# Mezzanine_Dual_H-Bridge.net
KiCad netlist of a schematic drawn in EAGLE
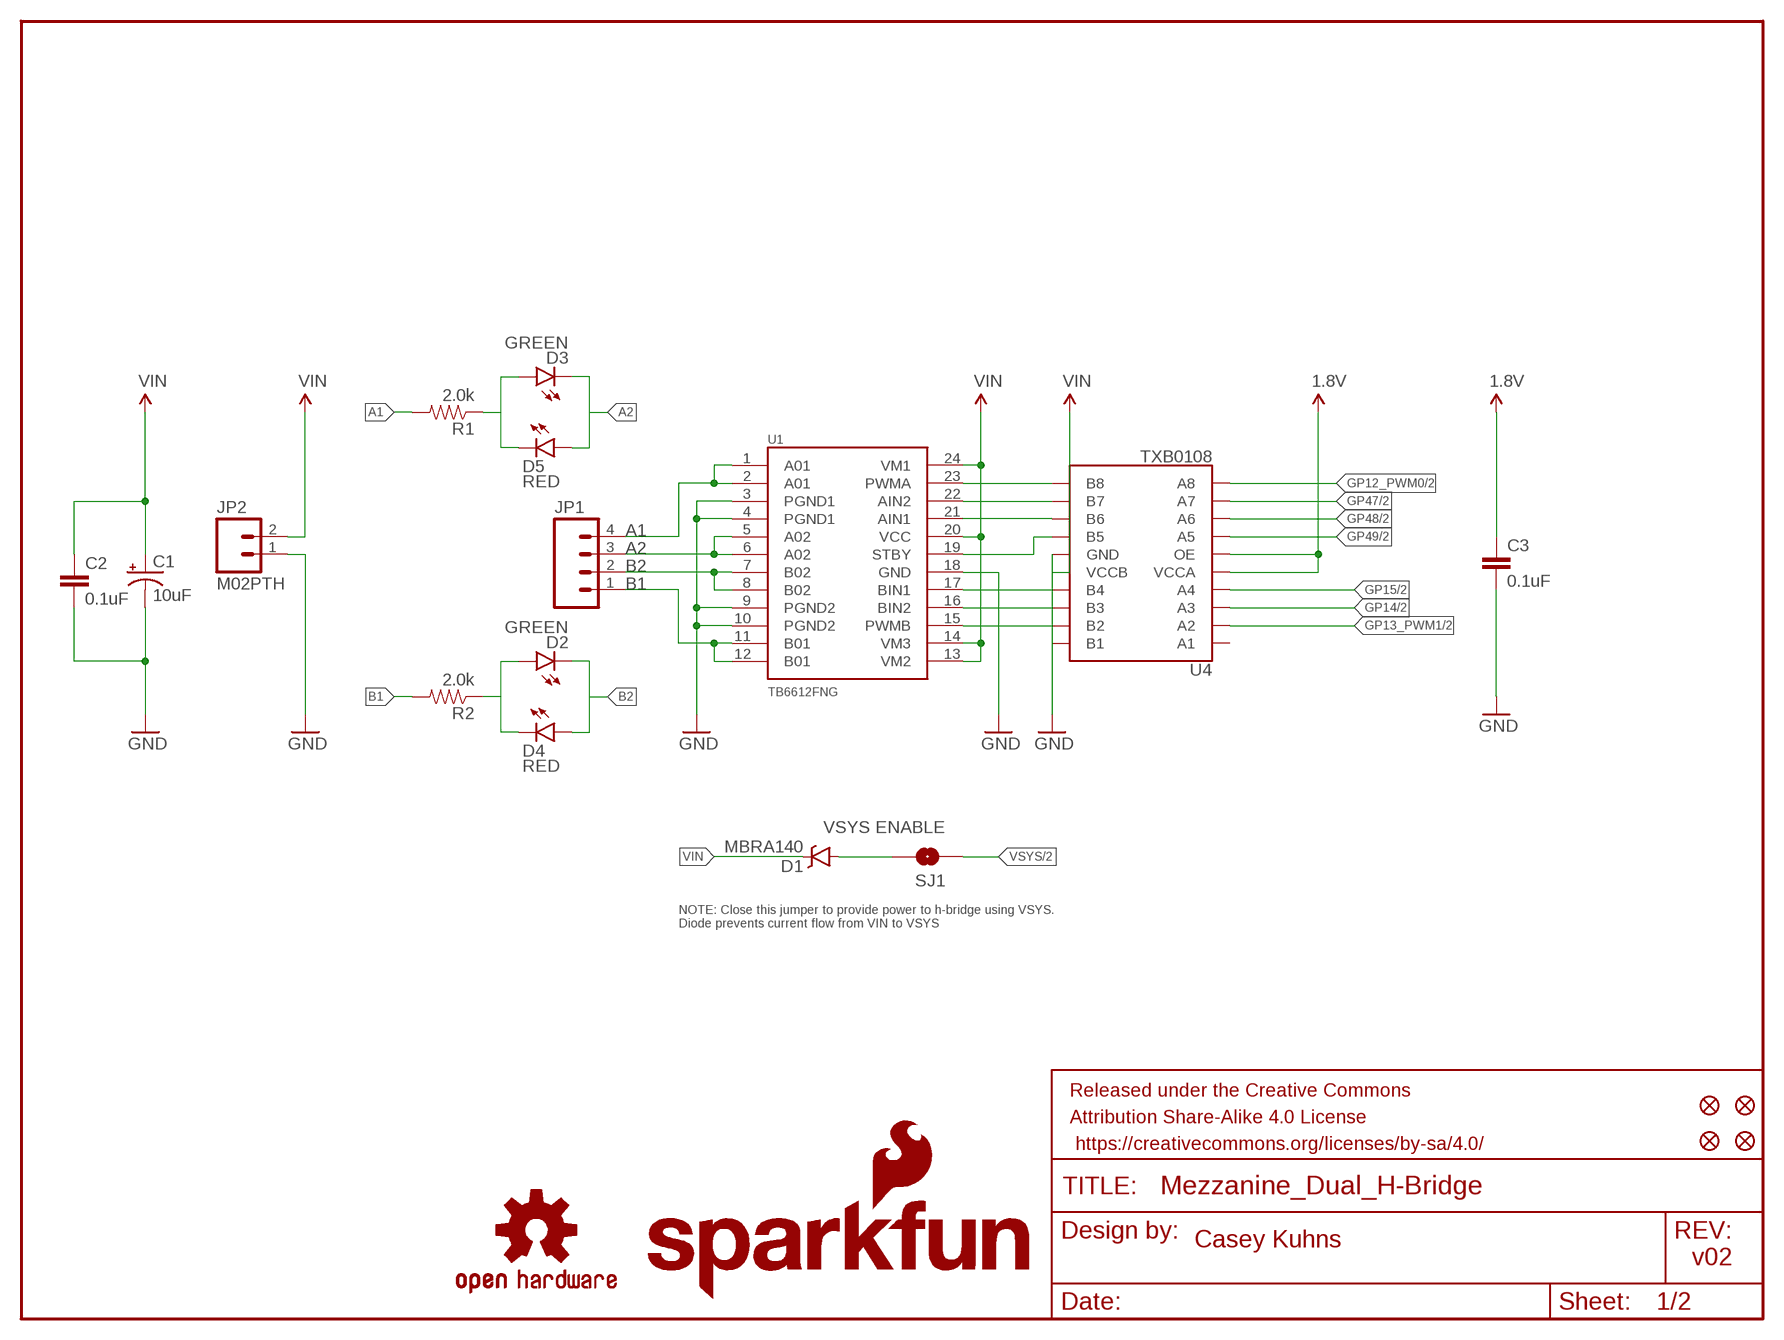
[diagram p0: schematic, sheet 1]
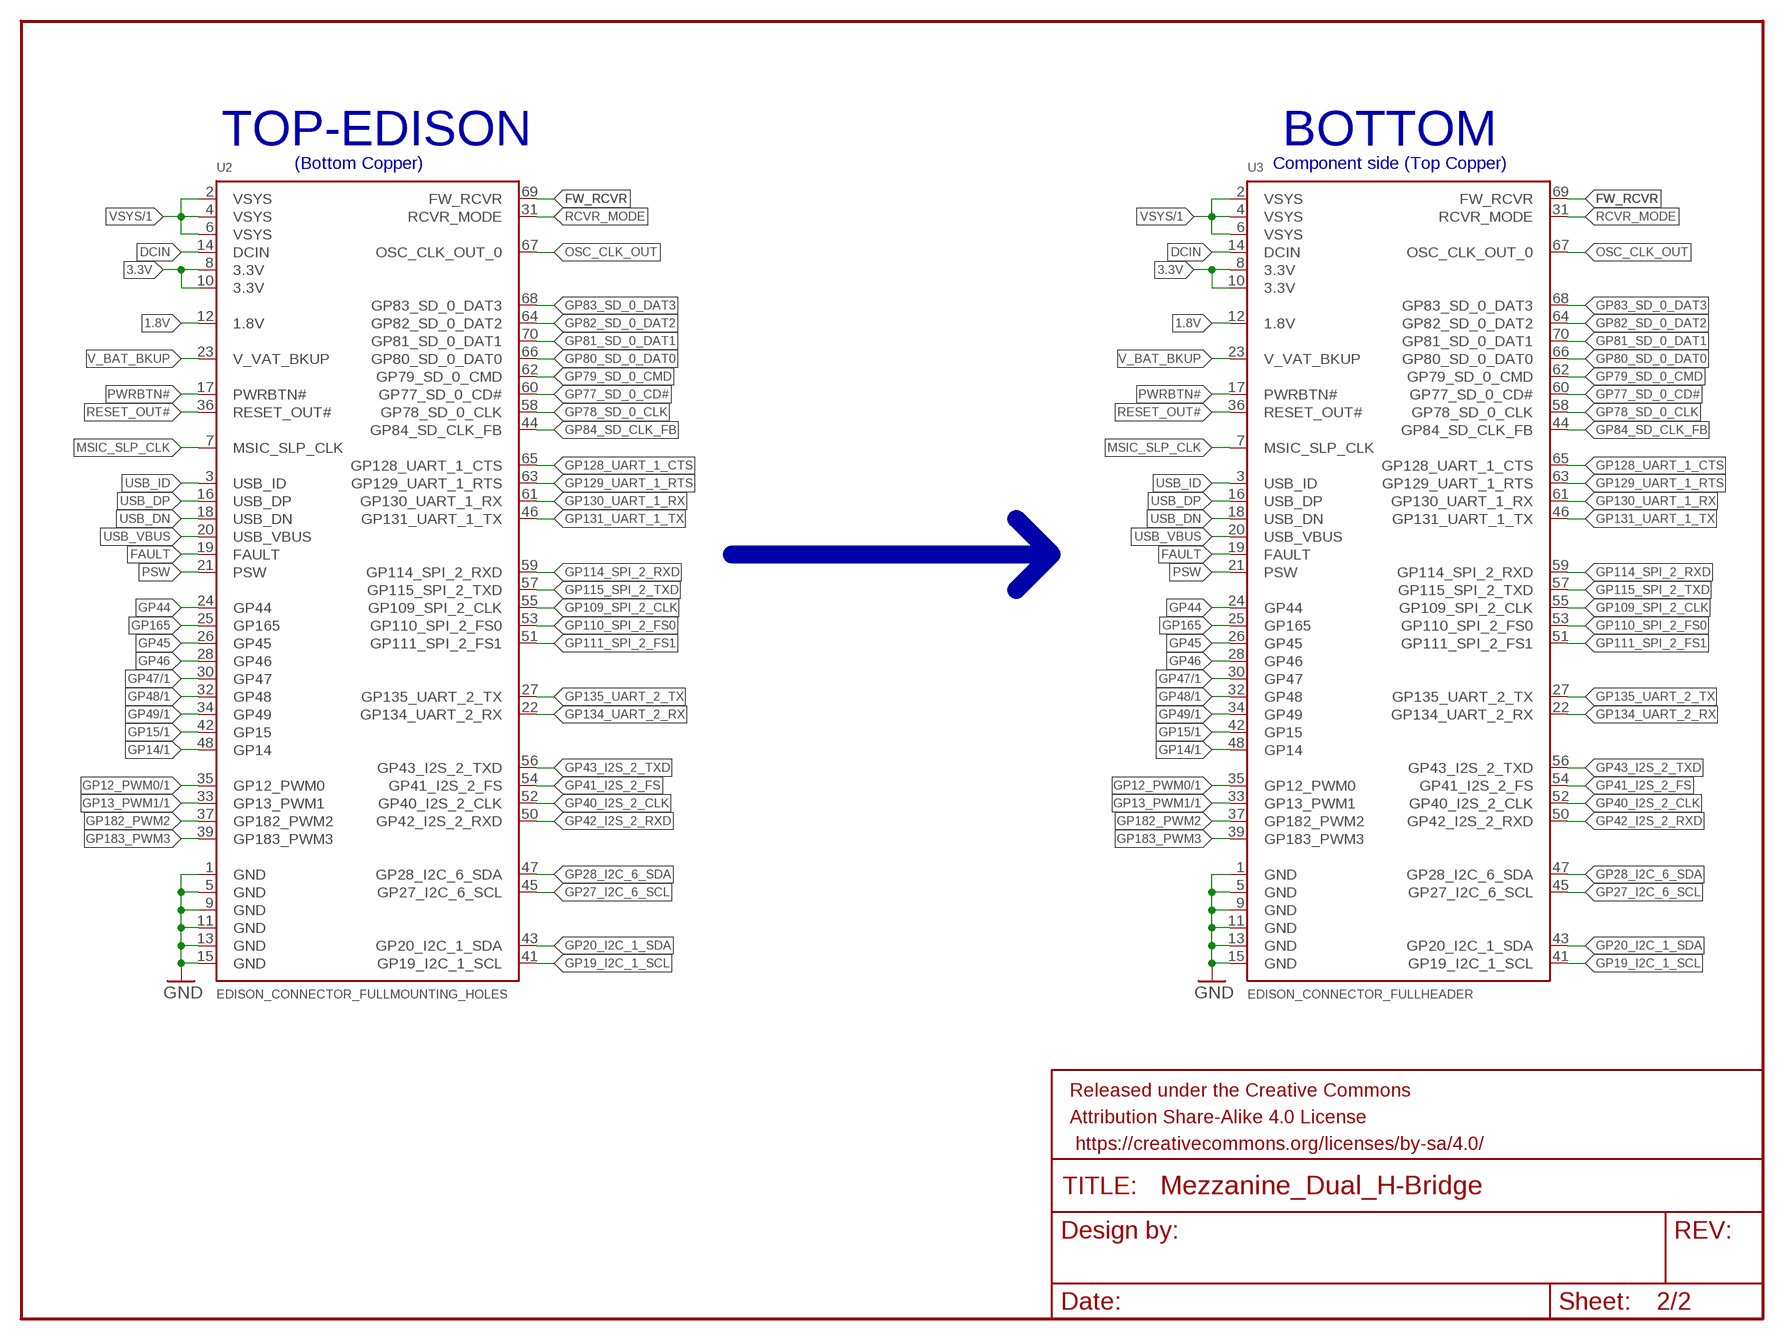
[diagram p1: schematic, sheet 2]

(export (version "E")
  (design (tool "Eeschema 10.0.6"))
  (components
    (comp (ref "FRAME2")
      (value "FRAME-LETTER")
      (footprint "eagle-import:CREATIVE_COMMONS")
      (libsource (lib "eagle-import") (part "FRAME-LETTER"))
    )
    (comp (ref "U2")
      (value "EDISON_CONNECTOR_FULLMOUNTING_HOLES")
      (footprint "eagle-import:EDISON_DAUGHTER")
      (libsource (lib "eagle-import") (part "EDISON_CONNECTOR_FULLMOUNTING_HOLES"))
    )
    (comp (ref "U3")
      (value "EDISON_CONNECTOR_FULLHEADER")
      (footprint "eagle-import:DF40C-70DP-0.4(51)")
      (libsource (lib "eagle-import") (part "EDISON_CONNECTOR_FULLHEADER"))
    )
    (comp (ref "C1")
      (value "10uF")
      (footprint "eagle-import:EIA3216")
      (libsource (lib "eagle-import") (part "10UF-16V-10%(TANT)"))
    )
    (comp (ref "C2")
      (value "0.1uF")
      (footprint "eagle-import:0603-CAP")
      (libsource (lib "eagle-import") (part "0.1UF-25V(+80/-20%)(0603)"))
    )
    (comp (ref "C3")
      (value "0.1uF")
      (footprint "eagle-import:0603-CAP")
      (libsource (lib "eagle-import") (part "0.1UF-25V(+80/-20%)(0603)"))
    )
    (comp (ref "D1")
      (value "MBRA140")
      (footprint "eagle-import:SMA-DIODE")
      (libsource (lib "eagle-import") (part "DIODE-SCHOTTKY-MBRA140"))
    )
    (comp (ref "D2")
      (value "GREEN")
      (footprint "eagle-import:LED-0603")
      (libsource (lib "eagle-import") (part "LED-GREEN0603"))
    )
    (comp (ref "D3")
      (value "GREEN")
      (footprint "eagle-import:LED-0603")
      (libsource (lib "eagle-import") (part "LED-GREEN0603"))
    )
    (comp (ref "D4")
      (value "RED")
      (footprint "eagle-import:LED-0603")
      (libsource (lib "eagle-import") (part "LED-RED0603"))
    )
    (comp (ref "D5")
      (value "RED")
      (footprint "eagle-import:LED-0603")
      (libsource (lib "eagle-import") (part "LED-RED0603"))
    )
    (comp (ref "FID1")
      (value "FIDUCIAL1X2")
      (footprint "eagle-import:FIDUCIAL-1X2")
      (libsource (lib "eagle-import") (part "FIDUCIAL1X2"))
    )
    (comp (ref "FID2")
      (value "FIDUCIAL1X2")
      (footprint "eagle-import:FIDUCIAL-1X2")
      (libsource (lib "eagle-import") (part "FIDUCIAL1X2"))
    )
    (comp (ref "FID3")
      (value "FIDUCIAL1X2")
      (footprint "eagle-import:FIDUCIAL-1X2")
      (libsource (lib "eagle-import") (part "FIDUCIAL1X2"))
    )
    (comp (ref "FID4")
      (value "FIDUCIAL1X2")
      (footprint "eagle-import:FIDUCIAL-1X2")
      (libsource (lib "eagle-import") (part "FIDUCIAL1X2"))
    )
    (comp (ref "FRAME1")
      (value "FRAME-LETTER")
      (footprint "eagle-import:CREATIVE_COMMONS")
      (libsource (lib "eagle-import") (part "FRAME-LETTER"))
    )
    (comp (ref "JP1")
      (value "M04PTH")
      (footprint "eagle-import:1X04")
      (libsource (lib "eagle-import") (part "M04PTH"))
    )
    (comp (ref "JP2")
      (value "M02PTH")
      (footprint "eagle-import:1X02")
      (libsource (lib "eagle-import") (part "M02PTH"))
    )
    (comp (ref "LOGO1")
      (value "OSHW-LOGOS")
      (footprint "eagle-import:OSHW-LOGO-S")
      (libsource (lib "eagle-import") (part "OSHW-LOGOS"))
    )
    (comp (ref "LOGO4")
      (value "SFE_LOGO_NAME_FLAME.1_INCH")
      (footprint "eagle-import:SFE_LOGO_NAME_FLAME_.1")
      (libsource (lib "eagle-import") (part "SFE_LOGO_NAME_FLAME.1_INCH"))
    )
    (comp (ref "R1")
      (value "2.0k")
      (footprint "eagle-import:0603-RES")
      (libsource (lib "eagle-import") (part "2.0KOHM1/10W5%(0603)"))
    )
    (comp (ref "R2")
      (value "2.0k")
      (footprint "eagle-import:0603-RES")
      (libsource (lib "eagle-import") (part "2.0KOHM1/10W5%(0603)"))
    )
    (comp (ref "SJ1")
      (value "VSYS ENABLE")
      (footprint "eagle-import:PAD-JUMPER-2-NO_YES_SILK")
      (libsource (lib "eagle-import") (part "JUMPER-PAD-2-NOYES_SILK"))
    )
    (comp (ref "U1")
      (value "TB6612FNG")
      (footprint "eagle-import:SSOP24")
      (libsource (lib "eagle-import") (part "TB6621FNG"))
    )
    (comp (ref "U4")
      (value "TXB0108")
      (footprint "eagle-import:UFDFN-20")
      (libsource (lib "eagle-import") (part "TXB0108"))
    )
  )
  (nets
    (net (code "1") (name "1.8V") (class "Default")
      (node (ref "C3") (pin "1") (pinfunction "1_1") (pintype "passive"))
      (node (ref "U2") (pin "12") (pinfunction "1.8V_12") (pintype "bidirectional"))
      (node (ref "U3") (pin "12") (pinfunction "1.8V_12") (pintype "bidirectional"))
      (node (ref "U4") (pin "5") (pinfunction "VCCA_5") (pintype "bidirectional"))
      (node (ref "U4") (pin "6") (pinfunction "OE_6") (pintype "bidirectional"))
    )
    (net (code "2") (name "3.3V") (class "Default")
      (node (ref "U2") (pin "10") (pinfunction "3.3V_10") (pintype "bidirectional"))
      (node (ref "U2") (pin "8") (pinfunction "3.3V_8") (pintype "bidirectional"))
      (node (ref "U3") (pin "10") (pinfunction "3.3V_10") (pintype "bidirectional"))
      (node (ref "U3") (pin "8") (pinfunction "3.3V_8") (pintype "bidirectional"))
    )
    (net (code "3") (name "A1") (class "Default")
      (node (ref "JP1") (pin "4") (pinfunction "4_4") (pintype "passive"))
      (node (ref "R1") (pin "2") (pinfunction "2_2") (pintype "passive"))
      (node (ref "U1") (pin "1") (pinfunction "A01_1") (pintype "bidirectional"))
      (node (ref "U1") (pin "2") (pinfunction "A01_2") (pintype "bidirectional"))
    )
    (net (code "4") (name "A2") (class "Default")
      (node (ref "D3") (pin "C") (pinfunction "C_C") (pintype "passive"))
      (node (ref "D5") (pin "A") (pinfunction "A_A") (pintype "passive"))
      (node (ref "JP1") (pin "3") (pinfunction "3_3") (pintype "passive"))
      (node (ref "U1") (pin "5") (pinfunction "A02_5") (pintype "bidirectional"))
      (node (ref "U1") (pin "6") (pinfunction "A02_6") (pintype "bidirectional"))
    )
    (net (code "5") (name "B1") (class "Default")
      (node (ref "JP1") (pin "1") (pinfunction "1_1") (pintype "passive"))
      (node (ref "R2") (pin "2") (pinfunction "2_2") (pintype "passive"))
      (node (ref "U1") (pin "11") (pinfunction "B01_11") (pintype "bidirectional"))
      (node (ref "U1") (pin "12") (pinfunction "B01_12") (pintype "bidirectional"))
    )
    (net (code "6") (name "B2") (class "Default")
      (node (ref "D2") (pin "C") (pinfunction "C_C") (pintype "passive"))
      (node (ref "D4") (pin "A") (pinfunction "A_A") (pintype "passive"))
      (node (ref "JP1") (pin "2") (pinfunction "2_2") (pintype "passive"))
      (node (ref "U1") (pin "7") (pinfunction "B02_7") (pintype "bidirectional"))
      (node (ref "U1") (pin "8") (pinfunction "B02_8") (pintype "bidirectional"))
    )
    (net (code "7") (name "DCIN") (class "Default")
      (node (ref "U2") (pin "14") (pinfunction "DCIN_14") (pintype "bidirectional"))
      (node (ref "U3") (pin "14") (pinfunction "DCIN_14") (pintype "bidirectional"))
    )
    (net (code "8") (name "FAULT") (class "Default")
      (node (ref "U2") (pin "19") (pinfunction "FAULT_19") (pintype "bidirectional"))
      (node (ref "U3") (pin "19") (pinfunction "FAULT_19") (pintype "bidirectional"))
    )
    (net (code "9") (name "FW_RCVR") (class "Default")
      (node (ref "U2") (pin "69") (pinfunction "FW_RCVR_69") (pintype "bidirectional"))
      (node (ref "U3") (pin "69") (pinfunction "FW_RCVR_69") (pintype "bidirectional"))
    )
    (net (code "10") (name "GND") (class "Default")
      (node (ref "C1") (pin "C") (pinfunction "-_C") (pintype "passive"))
      (node (ref "C2") (pin "2") (pinfunction "2_2") (pintype "passive"))
      (node (ref "C3") (pin "2") (pinfunction "2_2") (pintype "passive"))
      (node (ref "JP2") (pin "1") (pinfunction "1_1") (pintype "passive"))
      (node (ref "U1") (pin "10") (pinfunction "PGND2_10") (pintype "bidirectional"))
      (node (ref "U1") (pin "18") (pinfunction "GND_18") (pintype "bidirectional"))
      (node (ref "U1") (pin "3") (pinfunction "PGND1_3") (pintype "bidirectional"))
      (node (ref "U1") (pin "4") (pinfunction "PGND1_4") (pintype "bidirectional"))
      (node (ref "U1") (pin "9") (pinfunction "PGND2_9") (pintype "bidirectional"))
      (node (ref "U2") (pin "1") (pinfunction "GND_1") (pintype "bidirectional"))
      (node (ref "U2") (pin "11") (pinfunction "GND_11") (pintype "bidirectional"))
      (node (ref "U2") (pin "13") (pinfunction "GND_13") (pintype "bidirectional"))
      (node (ref "U2") (pin "15") (pinfunction "GND_15") (pintype "bidirectional"))
      (node (ref "U2") (pin "5") (pinfunction "GND_5") (pintype "bidirectional"))
      (node (ref "U2") (pin "9") (pinfunction "GND_9") (pintype "bidirectional"))
      (node (ref "U3") (pin "1") (pinfunction "GND_1") (pintype "bidirectional"))
      (node (ref "U3") (pin "11") (pinfunction "GND_11") (pintype "bidirectional"))
      (node (ref "U3") (pin "13") (pinfunction "GND_13") (pintype "bidirectional"))
      (node (ref "U3") (pin "15") (pinfunction "GND_15") (pintype "bidirectional"))
      (node (ref "U3") (pin "5") (pinfunction "GND_5") (pintype "bidirectional"))
      (node (ref "U3") (pin "9") (pinfunction "GND_9") (pintype "bidirectional"))
      (node (ref "U4") (pin "15") (pinfunction "GND_15") (pintype "bidirectional"))
    )
    (net (code "11") (name "GP12_PWM0") (class "Default")
      (node (ref "U2") (pin "35") (pinfunction "GP12_PWM0_35") (pintype "bidirectional"))
      (node (ref "U3") (pin "35") (pinfunction "GP12_PWM0_35") (pintype "bidirectional"))
      (node (ref "U4") (pin "10") (pinfunction "A8_10") (pintype "bidirectional"))
    )
    (net (code "12") (name "GP13_PWM1") (class "Default")
      (node (ref "U2") (pin "33") (pinfunction "GP13_PWM1_33") (pintype "bidirectional"))
      (node (ref "U3") (pin "33") (pinfunction "GP13_PWM1_33") (pintype "bidirectional"))
      (node (ref "U4") (pin "2") (pinfunction "A2_2") (pintype "bidirectional"))
    )
    (net (code "13") (name "GP14") (class "Default")
      (node (ref "U2") (pin "48") (pinfunction "GP14_48") (pintype "bidirectional"))
      (node (ref "U3") (pin "48") (pinfunction "GP14_48") (pintype "bidirectional"))
      (node (ref "U4") (pin "3") (pinfunction "A3_3") (pintype "bidirectional"))
    )
    (net (code "14") (name "GP15") (class "Default")
      (node (ref "U2") (pin "42") (pinfunction "GP15_42") (pintype "bidirectional"))
      (node (ref "U3") (pin "42") (pinfunction "GP15_42") (pintype "bidirectional"))
      (node (ref "U4") (pin "4") (pinfunction "A4_4") (pintype "bidirectional"))
    )
    (net (code "15") (name "GP19_I2C_1_SCL") (class "Default")
      (node (ref "U2") (pin "41") (pinfunction "GP19_I2C_1_SCL_41") (pintype "bidirectional"))
      (node (ref "U3") (pin "41") (pinfunction "GP19_I2C_1_SCL_41") (pintype "bidirectional"))
    )
    (net (code "16") (name "GP20_I2C_1_SDA") (class "Default")
      (node (ref "U2") (pin "43") (pinfunction "GP20_I2C_1_SDA_43") (pintype "bidirectional"))
      (node (ref "U3") (pin "43") (pinfunction "GP20_I2C_1_SDA_43") (pintype "bidirectional"))
    )
    (net (code "17") (name "GP27_I2C_6_SCL") (class "Default")
      (node (ref "U2") (pin "45") (pinfunction "GP27_I2C_6_SCL_45") (pintype "bidirectional"))
      (node (ref "U3") (pin "45") (pinfunction "GP27_I2C_6_SCL_45") (pintype "bidirectional"))
    )
    (net (code "18") (name "GP28_I2C_6_SDA") (class "Default")
      (node (ref "U2") (pin "47") (pinfunction "GP28_I2C_6_SDA_47") (pintype "bidirectional"))
      (node (ref "U3") (pin "47") (pinfunction "GP28_I2C_6_SDA_47") (pintype "bidirectional"))
    )
    (net (code "19") (name "GP40_I2S_2_CLK") (class "Default")
      (node (ref "U2") (pin "52") (pinfunction "GP40_I2S_2_CLK_52") (pintype "bidirectional"))
      (node (ref "U3") (pin "52") (pinfunction "GP40_I2S_2_CLK_52") (pintype "bidirectional"))
    )
    (net (code "20") (name "GP41_I2S_2_FS") (class "Default")
      (node (ref "U2") (pin "54") (pinfunction "GP41_I2S_2_FS_54") (pintype "bidirectional"))
      (node (ref "U3") (pin "54") (pinfunction "GP41_I2S_2_FS_54") (pintype "bidirectional"))
    )
    (net (code "21") (name "GP42_I2S_2_RXD") (class "Default")
      (node (ref "U2") (pin "50") (pinfunction "GP42_I2S_2_RXD_50") (pintype "bidirectional"))
      (node (ref "U3") (pin "50") (pinfunction "GP42_I2S_2_RXD_50") (pintype "bidirectional"))
    )
    (net (code "22") (name "GP43_I2S_2_TXD") (class "Default")
      (node (ref "U2") (pin "56") (pinfunction "GP43_I2S_2_TXD_56") (pintype "bidirectional"))
      (node (ref "U3") (pin "56") (pinfunction "GP43_I2S_2_TXD_56") (pintype "bidirectional"))
    )
    (net (code "23") (name "GP44") (class "Default")
      (node (ref "U2") (pin "24") (pinfunction "GP44_24") (pintype "bidirectional"))
      (node (ref "U3") (pin "24") (pinfunction "GP44_24") (pintype "bidirectional"))
    )
    (net (code "24") (name "GP45") (class "Default")
      (node (ref "U2") (pin "26") (pinfunction "GP45_26") (pintype "bidirectional"))
      (node (ref "U3") (pin "26") (pinfunction "GP45_26") (pintype "bidirectional"))
    )
    (net (code "25") (name "GP46") (class "Default")
      (node (ref "U2") (pin "28") (pinfunction "GP46_28") (pintype "bidirectional"))
      (node (ref "U3") (pin "28") (pinfunction "GP46_28") (pintype "bidirectional"))
    )
    (net (code "26") (name "GP47") (class "Default")
      (node (ref "U2") (pin "30") (pinfunction "GP47_30") (pintype "bidirectional"))
      (node (ref "U3") (pin "30") (pinfunction "GP47_30") (pintype "bidirectional"))
      (node (ref "U4") (pin "9") (pinfunction "A7_9") (pintype "bidirectional"))
    )
    (net (code "27") (name "GP48") (class "Default")
      (node (ref "U2") (pin "32") (pinfunction "GP48_32") (pintype "bidirectional"))
      (node (ref "U3") (pin "32") (pinfunction "GP48_32") (pintype "bidirectional"))
      (node (ref "U4") (pin "8") (pinfunction "A6_8") (pintype "bidirectional"))
    )
    (net (code "28") (name "GP49") (class "Default")
      (node (ref "U2") (pin "34") (pinfunction "GP49_34") (pintype "bidirectional"))
      (node (ref "U3") (pin "34") (pinfunction "GP49_34") (pintype "bidirectional"))
      (node (ref "U4") (pin "7") (pinfunction "A5_7") (pintype "bidirectional"))
    )
    (net (code "29") (name "GP77_SD_0_CD#") (class "Default")
      (node (ref "U2") (pin "60") (pinfunction "GP77_SD_0_CD#_60") (pintype "bidirectional"))
      (node (ref "U3") (pin "60") (pinfunction "GP77_SD_0_CD#_60") (pintype "bidirectional"))
    )
    (net (code "30") (name "GP78_SD_0_CLK") (class "Default")
      (node (ref "U2") (pin "58") (pinfunction "GP78_SD_0_CLK_58") (pintype "bidirectional"))
      (node (ref "U3") (pin "58") (pinfunction "GP78_SD_0_CLK_58") (pintype "bidirectional"))
    )
    (net (code "31") (name "GP79_SD_0_CMD") (class "Default")
      (node (ref "U2") (pin "62") (pinfunction "GP79_SD_0_CMD_62") (pintype "bidirectional"))
      (node (ref "U3") (pin "62") (pinfunction "GP79_SD_0_CMD_62") (pintype "bidirectional"))
    )
    (net (code "32") (name "GP80_SD_0_DAT0") (class "Default")
      (node (ref "U2") (pin "66") (pinfunction "GP80_SD_0_DAT0_66") (pintype "bidirectional"))
      (node (ref "U3") (pin "66") (pinfunction "GP80_SD_0_DAT0_66") (pintype "bidirectional"))
    )
    (net (code "33") (name "GP81_SD_0_DAT1") (class "Default")
      (node (ref "U2") (pin "70") (pinfunction "GP81_SD_0_DAT1_70") (pintype "bidirectional"))
      (node (ref "U3") (pin "70") (pinfunction "GP81_SD_0_DAT1_70") (pintype "bidirectional"))
    )
    (net (code "34") (name "GP82_SD_0_DAT2") (class "Default")
      (node (ref "U2") (pin "64") (pinfunction "GP82_SD_0_DAT2_64") (pintype "bidirectional"))
      (node (ref "U3") (pin "64") (pinfunction "GP82_SD_0_DAT2_64") (pintype "bidirectional"))
    )
    (net (code "35") (name "GP83_SD_0_DAT3") (class "Default")
      (node (ref "U2") (pin "68") (pinfunction "GP83_SD_0_DAT3_68") (pintype "bidirectional"))
      (node (ref "U3") (pin "68") (pinfunction "GP83_SD_0_DAT3_68") (pintype "bidirectional"))
    )
    (net (code "36") (name "GP84_SD_CLK_FB") (class "Default")
      (node (ref "U2") (pin "44") (pinfunction "GP84_SD_CLK_FB_44") (pintype "bidirectional"))
      (node (ref "U3") (pin "44") (pinfunction "GP84_SD_CLK_FB_44") (pintype "bidirectional"))
    )
    (net (code "37") (name "GP109_SPI_2_CLK") (class "Default")
      (node (ref "U2") (pin "55") (pinfunction "GP109_SPI_2_CLK_55") (pintype "bidirectional"))
      (node (ref "U3") (pin "55") (pinfunction "GP109_SPI_2_CLK_55") (pintype "bidirectional"))
    )
    (net (code "38") (name "GP110_SPI_2_FS0") (class "Default")
      (node (ref "U2") (pin "53") (pinfunction "GP110_SPI_2_FS0_53") (pintype "bidirectional"))
      (node (ref "U3") (pin "53") (pinfunction "GP110_SPI_2_FS0_53") (pintype "bidirectional"))
    )
    (net (code "39") (name "GP111_SPI_2_FS1") (class "Default")
      (node (ref "U2") (pin "51") (pinfunction "GP111_SPI_2_FS1_51") (pintype "bidirectional"))
      (node (ref "U3") (pin "51") (pinfunction "GP111_SPI_2_FS1_51") (pintype "bidirectional"))
    )
    (net (code "40") (name "GP114_SPI_2_RXD") (class "Default")
      (node (ref "U2") (pin "59") (pinfunction "GP114_SPI_2_RXD_59") (pintype "bidirectional"))
      (node (ref "U3") (pin "59") (pinfunction "GP114_SPI_2_RXD_59") (pintype "bidirectional"))
    )
    (net (code "41") (name "GP115_SPI_2_TXD") (class "Default")
      (node (ref "U2") (pin "57") (pinfunction "GP115_SPI_2_TXD_57") (pintype "bidirectional"))
      (node (ref "U3") (pin "57") (pinfunction "GP115_SPI_2_TXD_57") (pintype "bidirectional"))
    )
    (net (code "42") (name "GP128_UART_1_CTS") (class "Default")
      (node (ref "U2") (pin "65") (pinfunction "GP128_UART_1_CTS_65") (pintype "bidirectional"))
      (node (ref "U3") (pin "65") (pinfunction "GP128_UART_1_CTS_65") (pintype "bidirectional"))
    )
    (net (code "43") (name "GP129_UART_1_RTS") (class "Default")
      (node (ref "U2") (pin "63") (pinfunction "GP129_UART_1_RTS_63") (pintype "bidirectional"))
      (node (ref "U3") (pin "63") (pinfunction "GP129_UART_1_RTS_63") (pintype "bidirectional"))
    )
    (net (code "44") (name "GP130_UART_1_RX") (class "Default")
      (node (ref "U2") (pin "61") (pinfunction "GP130_UART_1_RX_61") (pintype "bidirectional"))
      (node (ref "U3") (pin "61") (pinfunction "GP130_UART_1_RX_61") (pintype "bidirectional"))
    )
    (net (code "45") (name "GP131_UART_1_TX") (class "Default")
      (node (ref "U2") (pin "46") (pinfunction "GP131_UART_1_TX_46") (pintype "bidirectional"))
      (node (ref "U3") (pin "46") (pinfunction "GP131_UART_1_TX_46") (pintype "bidirectional"))
    )
    (net (code "46") (name "GP134_UART_2_RX") (class "Default")
      (node (ref "U2") (pin "22") (pinfunction "GP134_UART_2_RX_22") (pintype "bidirectional"))
      (node (ref "U3") (pin "22") (pinfunction "GP134_UART_2_RX_22") (pintype "bidirectional"))
    )
    (net (code "47") (name "GP135_UART_2_TX") (class "Default")
      (node (ref "U2") (pin "27") (pinfunction "GP135_UART_2_TX_27") (pintype "bidirectional"))
      (node (ref "U3") (pin "27") (pinfunction "GP135_UART_2_TX_27") (pintype "bidirectional"))
    )
    (net (code "48") (name "GP165") (class "Default")
      (node (ref "U2") (pin "25") (pinfunction "GP165_25") (pintype "bidirectional"))
      (node (ref "U3") (pin "25") (pinfunction "GP165_25") (pintype "bidirectional"))
    )
    (net (code "49") (name "GP182_PWM2") (class "Default")
      (node (ref "U2") (pin "37") (pinfunction "GP182_PWM2_37") (pintype "bidirectional"))
      (node (ref "U3") (pin "37") (pinfunction "GP182_PWM2_37") (pintype "bidirectional"))
    )
    (net (code "50") (name "GP183_PWM3") (class "Default")
      (node (ref "U2") (pin "39") (pinfunction "GP183_PWM3_39") (pintype "bidirectional"))
      (node (ref "U3") (pin "39") (pinfunction "GP183_PWM3_39") (pintype "bidirectional"))
    )
    (net (code "51") (name "MSIC_SLP_CLK") (class "Default")
      (node (ref "U2") (pin "7") (pinfunction "MSIC_SLP_CLK_7") (pintype "bidirectional"))
      (node (ref "U3") (pin "7") (pinfunction "MSIC_SLP_CLK_7") (pintype "bidirectional"))
    )
    (net (code "52") (name "Net-(D1-PadA)") (class "Default")
      (node (ref "D1") (pin "A") (pinfunction "A_A") (pintype "passive"))
      (node (ref "SJ1") (pin "2") (pinfunction "2_2") (pintype "passive"))
    )
    (net (code "53") (name "Net-(D2-PadA)") (class "Default")
      (node (ref "D2") (pin "A") (pinfunction "A_A") (pintype "passive"))
      (node (ref "D4") (pin "C") (pinfunction "C_C") (pintype "passive"))
      (node (ref "R2") (pin "1") (pinfunction "1_1") (pintype "passive"))
    )
    (net (code "54") (name "Net-(D3-PadA)") (class "Default")
      (node (ref "D3") (pin "A") (pinfunction "A_A") (pintype "passive"))
      (node (ref "D5") (pin "C") (pinfunction "C_C") (pintype "passive"))
      (node (ref "R1") (pin "1") (pinfunction "1_1") (pintype "passive"))
    )
    (net (code "55") (name "Net-(U1-AIN1)") (class "Default")
      (node (ref "U1") (pin "21") (pinfunction "AIN1_21") (pintype "bidirectional"))
      (node (ref "U4") (pin "13") (pinfunction "B6_13") (pintype "bidirectional"))
    )
    (net (code "56") (name "Net-(U1-AIN2)") (class "Default")
      (node (ref "U1") (pin "22") (pinfunction "AIN2_22") (pintype "bidirectional"))
      (node (ref "U4") (pin "12") (pinfunction "B7_12") (pintype "bidirectional"))
    )
    (net (code "57") (name "Net-(U1-BIN1)") (class "Default")
      (node (ref "U1") (pin "17") (pinfunction "BIN1_17") (pintype "bidirectional"))
      (node (ref "U4") (pin "17") (pinfunction "B4_17") (pintype "bidirectional"))
    )
    (net (code "58") (name "Net-(U1-BIN2)") (class "Default")
      (node (ref "U1") (pin "16") (pinfunction "BIN2_16") (pintype "bidirectional"))
      (node (ref "U4") (pin "18") (pinfunction "B3_18") (pintype "bidirectional"))
    )
    (net (code "59") (name "Net-(U1-PWMA)") (class "Default")
      (node (ref "U1") (pin "23") (pinfunction "PWMA_23") (pintype "bidirectional"))
      (node (ref "U4") (pin "11") (pinfunction "B8_11") (pintype "bidirectional"))
    )
    (net (code "60") (name "Net-(U1-PWMB)") (class "Default")
      (node (ref "U1") (pin "15") (pinfunction "PWMB_15") (pintype "bidirectional"))
      (node (ref "U4") (pin "19") (pinfunction "B2_19") (pintype "bidirectional"))
    )
    (net (code "61") (name "Net-(U1-STBY)") (class "Default")
      (node (ref "U1") (pin "19") (pinfunction "STBY_19") (pintype "bidirectional"))
      (node (ref "U4") (pin "14") (pinfunction "B5_14") (pintype "bidirectional"))
    )
    (net (code "62") (name "OSC_CLK_OUT") (class "Default")
      (node (ref "U2") (pin "67") (pinfunction "OSC_CLK_OUT_0_67") (pintype "bidirectional"))
      (node (ref "U3") (pin "67") (pinfunction "OSC_CLK_OUT_0_67") (pintype "bidirectional"))
    )
    (net (code "63") (name "PSW") (class "Default")
      (node (ref "U2") (pin "21") (pinfunction "PSW_21") (pintype "bidirectional"))
      (node (ref "U3") (pin "21") (pinfunction "PSW_21") (pintype "bidirectional"))
    )
    (net (code "64") (name "PWRBTN#") (class "Default")
      (node (ref "U2") (pin "17") (pinfunction "PWRBTN#_17") (pintype "bidirectional"))
      (node (ref "U3") (pin "17") (pinfunction "PWRBTN#_17") (pintype "bidirectional"))
    )
    (net (code "65") (name "RCVR_MODE") (class "Default")
      (node (ref "U2") (pin "31") (pinfunction "RCVR_MODE_31") (pintype "bidirectional"))
      (node (ref "U3") (pin "31") (pinfunction "RCVR_MODE_31") (pintype "bidirectional"))
    )
    (net (code "66") (name "RESET_OUT#") (class "Default")
      (node (ref "U2") (pin "36") (pinfunction "RESET_OUT#_36") (pintype "bidirectional"))
      (node (ref "U3") (pin "36") (pinfunction "RESET_OUT#_36") (pintype "bidirectional"))
    )
    (net (code "67") (name "USB_DN") (class "Default")
      (node (ref "U2") (pin "18") (pinfunction "USB_DN_18") (pintype "bidirectional"))
      (node (ref "U3") (pin "18") (pinfunction "USB_DN_18") (pintype "bidirectional"))
    )
    (net (code "68") (name "USB_DP") (class "Default")
      (node (ref "U2") (pin "16") (pinfunction "USB_DP_16") (pintype "bidirectional"))
      (node (ref "U3") (pin "16") (pinfunction "USB_DP_16") (pintype "bidirectional"))
    )
    (net (code "69") (name "USB_ID") (class "Default")
      (node (ref "U2") (pin "3") (pinfunction "USB_ID_3") (pintype "bidirectional"))
      (node (ref "U3") (pin "3") (pinfunction "USB_ID_3") (pintype "bidirectional"))
    )
    (net (code "70") (name "USB_VBUS") (class "Default")
      (node (ref "U2") (pin "20") (pinfunction "USB_VBUS_20") (pintype "bidirectional"))
      (node (ref "U3") (pin "20") (pinfunction "USB_VBUS_20") (pintype "bidirectional"))
    )
    (net (code "71") (name "VIN") (class "Default")
      (node (ref "C1") (pin "A") (pinfunction "+_A") (pintype "passive"))
      (node (ref "C2") (pin "1") (pinfunction "1_1") (pintype "passive"))
      (node (ref "D1") (pin "C") (pinfunction "C_C") (pintype "passive"))
      (node (ref "JP2") (pin "2") (pinfunction "2_2") (pintype "passive"))
      (node (ref "U1") (pin "13") (pinfunction "VM2_13") (pintype "bidirectional"))
      (node (ref "U1") (pin "14") (pinfunction "VM3_14") (pintype "bidirectional"))
      (node (ref "U1") (pin "20") (pinfunction "VCC_20") (pintype "bidirectional"))
      (node (ref "U1") (pin "24") (pinfunction "VM1_24") (pintype "bidirectional"))
      (node (ref "U4") (pin "16") (pinfunction "VCCB_16") (pintype "bidirectional"))
    )
    (net (code "72") (name "VSYS") (class "Default")
      (node (ref "SJ1") (pin "1") (pinfunction "1_1") (pintype "passive"))
      (node (ref "U2") (pin "2") (pinfunction "VSYS_2") (pintype "bidirectional"))
      (node (ref "U2") (pin "4") (pinfunction "VSYS_4") (pintype "bidirectional"))
      (node (ref "U2") (pin "6") (pinfunction "VSYS_6") (pintype "bidirectional"))
      (node (ref "U3") (pin "2") (pinfunction "VSYS_2") (pintype "bidirectional"))
      (node (ref "U3") (pin "4") (pinfunction "VSYS_4") (pintype "bidirectional"))
      (node (ref "U3") (pin "6") (pinfunction "VSYS_6") (pintype "bidirectional"))
    )
    (net (code "73") (name "V_BAT_BKUP") (class "Default")
      (node (ref "U2") (pin "23") (pinfunction "V_VAT_BKUP_23") (pintype "bidirectional"))
      (node (ref "U3") (pin "23") (pinfunction "V_VAT_BKUP_23") (pintype "bidirectional"))
    )
    (net (code "74") (name "unconnected-(U4-A1-Pad1)") (class "Default")
      (node (ref "U4") (pin "1") (pinfunction "A1_1") (pintype "bidirectional"))
    )
    (net (code "75") (name "unconnected-(U4-B1-Pad20)") (class "Default")
      (node (ref "U4") (pin "20") (pinfunction "B1_20") (pintype "bidirectional"))
    )
  )
)
